# HotplateReflowSchematic.net
KiCad netlist of a schematic drawn in EAGLE
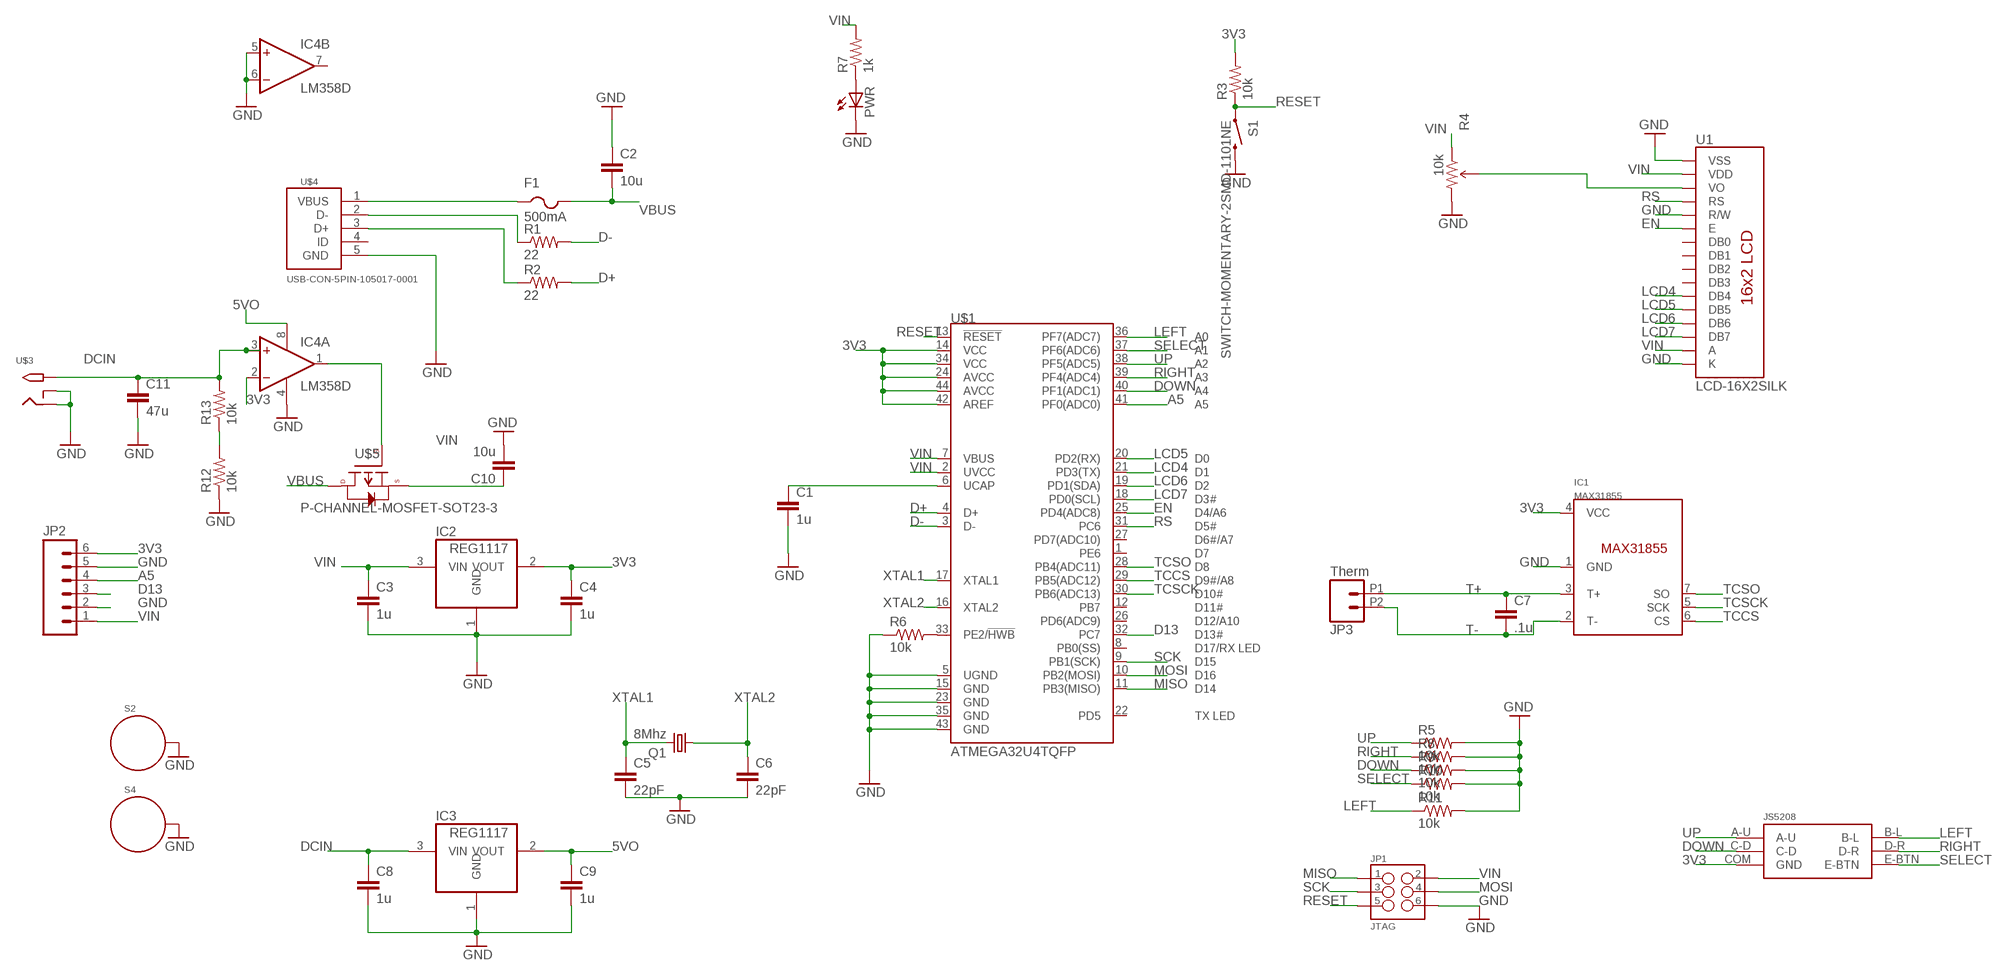
[diagram p0: schematic, sheet 1]

(export (version "E")
  (design (tool "Eeschema 10.0.6"))
  (components
    (comp (ref "C1")
      (value "1u")
      (footprint "eagle-import:0603-CAP")
      (libsource (lib "eagle-import") (part "SparkFun-Passives_CAP0603-CAP"))
    )
    (comp (ref "C2")
      (value "10u")
      (footprint "eagle-import:0603-CAP")
      (libsource (lib "eagle-import") (part "SparkFun-Passives_CAP0603-CAP"))
    )
    (comp (ref "C3")
      (value "1u")
      (footprint "eagle-import:0603-CAP")
      (libsource (lib "eagle-import") (part "SparkFun-Passives_CAP0603-CAP"))
    )
    (comp (ref "C4")
      (value "1u")
      (footprint "eagle-import:0603-CAP")
      (libsource (lib "eagle-import") (part "SparkFun-Passives_CAP0603-CAP"))
    )
    (comp (ref "C5")
      (value "22pF")
      (footprint "eagle-import:0603-CAP")
      (libsource (lib "eagle-import") (part "SparkFun-Passives_CAP0603-CAP"))
    )
    (comp (ref "C6")
      (value "22pF")
      (footprint "eagle-import:0603-CAP")
      (libsource (lib "eagle-import") (part "SparkFun-Passives_CAP0603-CAP"))
    )
    (comp (ref "C7")
      (value ".1u")
      (footprint "eagle-import:0603-CAP")
      (libsource (lib "eagle-import") (part "SparkFun-Passives_CAP0603-CAP"))
    )
    (comp (ref "C8")
      (value "1u")
      (footprint "eagle-import:0603-CAP")
      (libsource (lib "eagle-import") (part "CAP0603-CAP"))
    )
    (comp (ref "C9")
      (value "1u")
      (footprint "eagle-import:0603-CAP")
      (libsource (lib "eagle-import") (part "CAP0603-CAP"))
    )
    (comp (ref "C10")
      (value "10u")
      (footprint "eagle-import:0603-CAP")
      (libsource (lib "eagle-import") (part "CAP0603-CAP"))
    )
    (comp (ref "C11")
      (value "47u")
      (footprint "eagle-import:0603-CAP")
      (libsource (lib "eagle-import") (part "SparkFun-Passives_CAP0603-CAP"))
    )
    (comp (ref "F1")
      (value "500mA")
      (footprint "eagle-import:1812")
      (libsource (lib "eagle-import") (part "PTCFUSE-1812"))
    )
    (comp (ref "IC1")
      (value "MAX31855")
      (footprint "eagle-import:SOIC8")
      (libsource (lib "eagle-import") (part "MAX31855"))
    )
    (comp (ref "IC2")
      (value "REG1117")
      (footprint "eagle-import:SOT223")
      (libsource (lib "eagle-import") (part "REG1117"))
    )
    (comp (ref "IC3")
      (value "REG1117")
      (footprint "eagle-import:SOT223")
      (libsource (lib "eagle-import") (part "REG1117"))
    )
    (comp (ref "IC4")
      (value "LM358D")
      (footprint "eagle-import:SO08")
      (libsource (lib "eagle-import") (part "LM358D"))
    )
    (comp (ref "JP1")
      (value "JTAG")
      (footprint "eagle-import:2X3-SHROUDED")
      (libsource (lib "eagle-import") (part "M03X2SHROUD"))
    )
    (comp (ref "JP2")
      (value "M06LOCK")
      (footprint "eagle-import:1X06_LOCK")
      (libsource (lib "eagle-import") (part "M06LOCK"))
    )
    (comp (ref "JP3")
      (value "Therm")
      (footprint "eagle-import:1X02_2.54_SCREWTERM")
      (libsource (lib "eagle-import") (part "M022.54MM_SCREWTERM"))
    )
    (comp (ref "PWR")
      (value "LEDCHIP-LED0603")
      (footprint "eagle-import:CHIP-LED0603")
      (libsource (lib "eagle-import") (part "LEDCHIP-LED0603"))
    )
    (comp (ref "Q1")
      (value "8Mhz")
      (footprint "eagle-import:HC49UP")
      (libsource (lib "eagle-import") (part "CRYSTALHC49UP"))
    )
    (comp (ref "R1")
      (value "22")
      (footprint "eagle-import:0603-RES")
      (libsource (lib "eagle-import") (part "RESISTOR0603-RES"))
    )
    (comp (ref "R2")
      (value "22")
      (footprint "eagle-import:0603-RES")
      (libsource (lib "eagle-import") (part "RESISTOR0603-RES"))
    )
    (comp (ref "R3")
      (value "10k")
      (footprint "eagle-import:0603-RES")
      (libsource (lib "eagle-import") (part "RESISTOR0603-RES"))
    )
    (comp (ref "R4")
      (value "10k")
      (footprint "eagle-import:TRIMPOT-5MM-V2")
      (libsource (lib "eagle-import") (part "TRIMPOT"))
    )
    (comp (ref "R5")
      (value "10k")
      (footprint "eagle-import:0603-RES")
      (libsource (lib "eagle-import") (part "RESISTOR0603-RES"))
    )
    (comp (ref "R6")
      (value "10k")
      (footprint "eagle-import:0603-RES")
      (libsource (lib "eagle-import") (part "RESISTOR0603"))
    )
    (comp (ref "R7")
      (value "1k")
      (footprint "eagle-import:0603-RES")
      (libsource (lib "eagle-import") (part "RESISTOR0603"))
    )
    (comp (ref "R8")
      (value "10k")
      (footprint "eagle-import:0603-RES")
      (libsource (lib "eagle-import") (part "RESISTOR0603-RES"))
    )
    (comp (ref "R9")
      (value "10k")
      (footprint "eagle-import:0603-RES")
      (libsource (lib "eagle-import") (part "RESISTOR0603-RES"))
    )
    (comp (ref "R10")
      (value "10k")
      (footprint "eagle-import:0603-RES")
      (libsource (lib "eagle-import") (part "RESISTOR0603-RES"))
    )
    (comp (ref "R11")
      (value "10k")
      (footprint "eagle-import:0603-RES")
      (libsource (lib "eagle-import") (part "RESISTOR0603-RES"))
    )
    (comp (ref "R12")
      (value "10k")
      (footprint "eagle-import:0603-RES")
      (libsource (lib "eagle-import") (part "RESISTOR0603-RES"))
    )
    (comp (ref "R13")
      (value "10k")
      (footprint "eagle-import:0603-RES")
      (libsource (lib "eagle-import") (part "RESISTOR0603-RES"))
    )
    (comp (ref "S1")
      (value "SWITCH-MOMENTARY-2SMD-1101NE")
      (footprint "eagle-import:TACTILE-SWITCH-1101NE")
      (libsource (lib "eagle-import") (part "SWITCH-MOMENTARY-2SMD-1101NE"))
    )
    (comp (ref "S2")
      (value "STANDOFF_ELECTRICAL")
      (footprint "eagle-import:STANDOFF-ELECTRICAL")
      (libsource (lib "eagle-import") (part "STANDOFF_ELECTRICAL"))
    )
    (comp (ref "S4")
      (value "STANDOFF_ELECTRICAL")
      (footprint "eagle-import:STANDOFF-ELECTRICAL")
      (libsource (lib "eagle-import") (part "STANDOFF_ELECTRICAL"))
    )
    (comp (ref "U$1")
      (value "ATMEGA32U4TQFP")
      (footprint "eagle-import:SPARKFUN-DIGITALIC_TQFP44")
      (libsource (lib "eagle-import") (part "ATMEGA32U4TQFP"))
    )
    (comp (ref "U$2")
      (value "JS5208")
      (footprint "eagle-import:JS5208_PKG")
      (libsource (lib "eagle-import") (part "JS5208"))
    )
    (comp (ref "U$3")
      (value "2.1MMJACKTHM")
      (footprint "eagle-import:PJ-102A")
      (libsource (lib "eagle-import") (part "2.1MMJACKTHM"))
    )
    (comp (ref "U$4")
      (value "USB-CON-5PIN-105017-0001")
      (footprint "eagle-import:USB-MICRO-MOLEX-105017-0001")
      (libsource (lib "eagle-import") (part "USB-CON-5PIN-105017-0001"))
    )
    (comp (ref "U$5")
      (value "P-CHANNEL-MOSFET-SOT23-3")
      (footprint "eagle-import:SOT23-3")
      (libsource (lib "eagle-import") (part "P-CHANNEL-MOSFET-SOT23-3"))
    )
    (comp (ref "U1")
      (value "LCD-16X2SILK")
      (footprint "eagle-import:LCD-16X2")
      (libsource (lib "eagle-import") (part "LCD-16X2SILK"))
    )
  )
  (nets
    (net (code "1") (name "/3V3") (class "Default")
      (node (ref "C4") (pin "1") (pinfunction "1_1") (pintype "passive"))
      (node (ref "IC1") (pin "4") (pinfunction "VCC_4") (pintype "power_in"))
      (node (ref "IC2") (pin "2") (pinfunction "VOUT_2") (pintype "output"))
      (node (ref "IC4") (pin "2") (pinfunction "-IN_2") (pintype "input"))
      (node (ref "JP2") (pin "6") (pinfunction "6_6") (pintype "passive"))
      (node (ref "R3") (pin "2") (pinfunction "2_2") (pintype "passive"))
      (node (ref "U$1") (pin "14") (pinfunction "VCC_14") (pintype "bidirectional"))
      (node (ref "U$1") (pin "24") (pinfunction "AVCC_24") (pintype "bidirectional"))
      (node (ref "U$1") (pin "34") (pinfunction "VCC_34") (pintype "bidirectional"))
      (node (ref "U$1") (pin "42") (pinfunction "AREF_42") (pintype "bidirectional"))
      (node (ref "U$1") (pin "44") (pinfunction "AVCC_44") (pintype "bidirectional"))
      (node (ref "U$2") (pin "COM") (pinfunction "GND_COM") (pintype "bidirectional"))
    )
    (net (code "2") (name "/5VO") (class "Default")
      (node (ref "C9") (pin "1") (pinfunction "1_1") (pintype "passive"))
      (node (ref "IC3") (pin "2") (pinfunction "VOUT_2") (pintype "output"))
      (node (ref "IC4") (pin "8") (pinfunction "V+_8") (pintype "power_in"))
    )
    (net (code "3") (name "/A5") (class "Default")
      (node (ref "JP2") (pin "4") (pinfunction "4_4") (pintype "passive"))
      (node (ref "U$1") (pin "41") (pinfunction "PF0(ADC0)_41") (pintype "bidirectional"))
    )
    (net (code "4") (name "/D+") (class "Default")
      (node (ref "R2") (pin "2") (pinfunction "2_2") (pintype "passive"))
      (node (ref "U$1") (pin "4") (pinfunction "D+_4") (pintype "bidirectional"))
    )
    (net (code "5") (name "/D-") (class "Default")
      (node (ref "R1") (pin "2") (pinfunction "2_2") (pintype "passive"))
      (node (ref "U$1") (pin "3") (pinfunction "D-_3") (pintype "bidirectional"))
    )
    (net (code "6") (name "/D13") (class "Default")
      (node (ref "JP2") (pin "3") (pinfunction "3_3") (pintype "passive"))
      (node (ref "U$1") (pin "32") (pinfunction "PC7_32") (pintype "bidirectional"))
    )
    (net (code "7") (name "/DCIN") (class "Default")
      (node (ref "C11") (pin "1") (pinfunction "1_1") (pintype "passive"))
      (node (ref "C8") (pin "1") (pinfunction "1_1") (pintype "passive"))
      (node (ref "IC3") (pin "3") (pinfunction "VIN_3") (pintype "input"))
      (node (ref "IC4") (pin "3") (pinfunction "+IN_3") (pintype "input"))
      (node (ref "R13") (pin "2") (pinfunction "2_2") (pintype "passive"))
      (node (ref "U$3") (pin "TIP") (pinfunction "TIP_TIP") (pintype "bidirectional"))
    )
    (net (code "8") (name "/DOWN") (class "Default")
      (node (ref "R9") (pin "1") (pinfunction "1_1") (pintype "passive"))
      (node (ref "U$1") (pin "40") (pinfunction "PF1(ADC1)_40") (pintype "bidirectional"))
      (node (ref "U$2") (pin "C-D") (pinfunction "C-D_C-D") (pintype "bidirectional"))
    )
    (net (code "9") (name "/EN") (class "Default")
      (node (ref "U$1") (pin "25") (pinfunction "PD4(ADC8)_25") (pintype "bidirectional"))
      (node (ref "U1") (pin "6") (pinfunction "E_6") (pintype "input"))
    )
    (net (code "10") (name "/LCD4") (class "Default")
      (node (ref "U$1") (pin "21") (pinfunction "PD3(TX)_21") (pintype "bidirectional"))
      (node (ref "U1") (pin "11") (pinfunction "DB4_11") (pintype "bidirectional"))
    )
    (net (code "11") (name "/LCD5") (class "Default")
      (node (ref "U$1") (pin "20") (pinfunction "PD2(RX)_20") (pintype "bidirectional"))
      (node (ref "U1") (pin "12") (pinfunction "DB5_12") (pintype "bidirectional"))
    )
    (net (code "12") (name "/LCD6") (class "Default")
      (node (ref "U$1") (pin "19") (pinfunction "PD1(SDA)_19") (pintype "bidirectional"))
      (node (ref "U1") (pin "13") (pinfunction "DB6_13") (pintype "bidirectional"))
    )
    (net (code "13") (name "/LCD7") (class "Default")
      (node (ref "U$1") (pin "18") (pinfunction "PD0(SCL)_18") (pintype "bidirectional"))
      (node (ref "U1") (pin "14") (pinfunction "DB7_14") (pintype "bidirectional"))
    )
    (net (code "14") (name "/LEFT") (class "Default")
      (node (ref "R11") (pin "1") (pinfunction "1_1") (pintype "passive"))
      (node (ref "U$1") (pin "36") (pinfunction "PF7(ADC7)_36") (pintype "bidirectional"))
      (node (ref "U$2") (pin "B-L") (pinfunction "B-L_B-L") (pintype "bidirectional"))
    )
    (net (code "15") (name "/MISO") (class "Default")
      (node (ref "JP1") (pin "1") (pinfunction "1_1") (pintype "bidirectional"))
      (node (ref "U$1") (pin "11") (pinfunction "PB3(MISO)_11") (pintype "bidirectional"))
    )
    (net (code "16") (name "/MOSI") (class "Default")
      (node (ref "JP1") (pin "4") (pinfunction "4_4") (pintype "bidirectional"))
      (node (ref "U$1") (pin "10") (pinfunction "PB2(MOSI)_10") (pintype "bidirectional"))
    )
    (net (code "17") (name "/RESET") (class "Default")
      (node (ref "JP1") (pin "5") (pinfunction "5_5") (pintype "bidirectional"))
      (node (ref "R3") (pin "1") (pinfunction "1_1") (pintype "passive"))
      (node (ref "S1") (pin "1") (pinfunction "1_1") (pintype "passive"))
      (node (ref "U$1") (pin "13") (pinfunction "~{RESET}_13") (pintype "bidirectional"))
    )
    (net (code "18") (name "/RIGHT") (class "Default")
      (node (ref "R8") (pin "1") (pinfunction "1_1") (pintype "passive"))
      (node (ref "U$1") (pin "39") (pinfunction "PF4(ADC4)_39") (pintype "bidirectional"))
      (node (ref "U$2") (pin "D-R") (pinfunction "D-R_D-R") (pintype "bidirectional"))
    )
    (net (code "19") (name "/RS") (class "Default")
      (node (ref "U$1") (pin "31") (pinfunction "PC6_31") (pintype "bidirectional"))
      (node (ref "U1") (pin "4") (pinfunction "RS_4") (pintype "input"))
    )
    (net (code "20") (name "/SCK") (class "Default")
      (node (ref "JP1") (pin "3") (pinfunction "3_3") (pintype "bidirectional"))
      (node (ref "U$1") (pin "9") (pinfunction "PB1(SCK)_9") (pintype "bidirectional"))
    )
    (net (code "21") (name "/SELECT") (class "Default")
      (node (ref "R10") (pin "1") (pinfunction "1_1") (pintype "passive"))
      (node (ref "U$1") (pin "37") (pinfunction "PF6(ADC6)_37") (pintype "bidirectional"))
      (node (ref "U$2") (pin "E-BTN") (pinfunction "E-BTN_E-BTN") (pintype "bidirectional"))
    )
    (net (code "22") (name "/T+") (class "Default")
      (node (ref "C7") (pin "1") (pinfunction "1_1") (pintype "passive"))
      (node (ref "IC1") (pin "3") (pinfunction "T+_3") (pintype "input"))
      (node (ref "JP3") (pin "P1") (pinfunction "1_P1") (pintype "passive"))
    )
    (net (code "23") (name "/T-") (class "Default")
      (node (ref "C7") (pin "2") (pinfunction "2_2") (pintype "passive"))
      (node (ref "IC1") (pin "2") (pinfunction "T-_2") (pintype "input"))
      (node (ref "JP3") (pin "P2") (pinfunction "2_P2") (pintype "passive"))
    )
    (net (code "24") (name "/TCCS") (class "Default")
      (node (ref "IC1") (pin "6") (pinfunction "CS_6") (pintype "input"))
      (node (ref "U$1") (pin "29") (pinfunction "PB5(ADC12)_29") (pintype "bidirectional"))
    )
    (net (code "25") (name "/TCSCK") (class "Default")
      (node (ref "IC1") (pin "5") (pinfunction "SCK_5") (pintype "input"))
      (node (ref "U$1") (pin "30") (pinfunction "PB6(ADC13)_30") (pintype "bidirectional"))
    )
    (net (code "26") (name "/TCSO") (class "Default")
      (node (ref "IC1") (pin "7") (pinfunction "SO_7") (pintype "output"))
      (node (ref "U$1") (pin "28") (pinfunction "PB4(ADC11)_28") (pintype "bidirectional"))
    )
    (net (code "27") (name "/UP") (class "Default")
      (node (ref "R5") (pin "1") (pinfunction "1_1") (pintype "passive"))
      (node (ref "U$1") (pin "38") (pinfunction "PF5(ADC5)_38") (pintype "bidirectional"))
      (node (ref "U$2") (pin "A-U") (pinfunction "A-U_A-U") (pintype "bidirectional"))
    )
    (net (code "28") (name "/VBUS") (class "Default")
      (node (ref "C2") (pin "2") (pinfunction "2_2") (pintype "passive"))
      (node (ref "F1") (pin "2") (pinfunction "2_2") (pintype "passive"))
      (node (ref "U$5") (pin "3") (pinfunction "D_3") (pintype "passive"))
    )
    (net (code "29") (name "/VIN") (class "Default")
      (node (ref "C10") (pin "1") (pinfunction "1_1") (pintype "passive"))
      (node (ref "C3") (pin "1") (pinfunction "1_1") (pintype "passive"))
      (node (ref "IC2") (pin "3") (pinfunction "VIN_3") (pintype "input"))
      (node (ref "JP1") (pin "2") (pinfunction "2_2") (pintype "bidirectional"))
      (node (ref "JP2") (pin "1") (pinfunction "1_1") (pintype "passive"))
      (node (ref "R4") (pin "A") (pinfunction "CCW_A") (pintype "passive"))
      (node (ref "R7") (pin "2") (pinfunction "2_2") (pintype "passive"))
      (node (ref "U$1") (pin "2") (pinfunction "UVCC_2") (pintype "bidirectional"))
      (node (ref "U$1") (pin "7") (pinfunction "VBUS_7") (pintype "bidirectional"))
      (node (ref "U$5") (pin "2") (pinfunction "S_2") (pintype "passive"))
      (node (ref "U1") (pin "15") (pinfunction "A_15") (pintype "power_in"))
      (node (ref "U1") (pin "2") (pinfunction "VDD_2") (pintype "power_in"))
    )
    (net (code "30") (name "/XTAL1") (class "Default")
      (node (ref "C5") (pin "1") (pinfunction "1_1") (pintype "passive"))
      (node (ref "Q1") (pin "2") (pinfunction "2_2") (pintype "passive"))
      (node (ref "U$1") (pin "17") (pinfunction "XTAL1_17") (pintype "bidirectional"))
    )
    (net (code "31") (name "/XTAL2") (class "Default")
      (node (ref "C6") (pin "1") (pinfunction "1_1") (pintype "passive"))
      (node (ref "Q1") (pin "1") (pinfunction "1_1") (pintype "passive"))
      (node (ref "U$1") (pin "16") (pinfunction "XTAL2_16") (pintype "bidirectional"))
    )
    (net (code "32") (name "GND") (class "Default")
      (node (ref "C1") (pin "2") (pinfunction "2_2") (pintype "passive"))
      (node (ref "C10") (pin "2") (pinfunction "2_2") (pintype "passive"))
      (node (ref "C11") (pin "2") (pinfunction "2_2") (pintype "passive"))
      (node (ref "C2") (pin "1") (pinfunction "1_1") (pintype "passive"))
      (node (ref "C3") (pin "2") (pinfunction "2_2") (pintype "passive"))
      (node (ref "C4") (pin "2") (pinfunction "2_2") (pintype "passive"))
      (node (ref "C5") (pin "2") (pinfunction "2_2") (pintype "passive"))
      (node (ref "C6") (pin "2") (pinfunction "2_2") (pintype "passive"))
      (node (ref "C8") (pin "2") (pinfunction "2_2") (pintype "passive"))
      (node (ref "C9") (pin "2") (pinfunction "2_2") (pintype "passive"))
      (node (ref "IC1") (pin "1") (pinfunction "GND_1") (pintype "power_in"))
      (node (ref "IC2") (pin "1") (pinfunction "GND_1") (pintype "power_in"))
      (node (ref "IC3") (pin "1") (pinfunction "GND_1") (pintype "power_in"))
      (node (ref "IC4") (pin "4") (pinfunction "V-_4") (pintype "power_in"))
      (node (ref "IC4") (pin "5") (pinfunction "+IN_5") (pintype "input"))
      (node (ref "IC4") (pin "6") (pinfunction "-IN_6") (pintype "input"))
      (node (ref "JP1") (pin "6") (pinfunction "6_6") (pintype "bidirectional"))
      (node (ref "JP2") (pin "2") (pinfunction "2_2") (pintype "passive"))
      (node (ref "JP2") (pin "5") (pinfunction "5_5") (pintype "passive"))
      (node (ref "PWR") (pin "C") (pinfunction "C_C") (pintype "passive"))
      (node (ref "R10") (pin "2") (pinfunction "2_2") (pintype "passive"))
      (node (ref "R11") (pin "2") (pinfunction "2_2") (pintype "passive"))
      (node (ref "R12") (pin "1") (pinfunction "1_1") (pintype "passive"))
      (node (ref "R4") (pin "C") (pinfunction "CW_C") (pintype "passive"))
      (node (ref "R5") (pin "2") (pinfunction "2_2") (pintype "passive"))
      (node (ref "R6") (pin "1") (pinfunction "1_1") (pintype "passive"))
      (node (ref "R8") (pin "2") (pinfunction "2_2") (pintype "passive"))
      (node (ref "R9") (pin "2") (pinfunction "2_2") (pintype "passive"))
      (node (ref "S1") (pin "2") (pinfunction "2_2") (pintype "passive"))
      (node (ref "S2") (pin "P1") (pinfunction "P$1_P1") (pintype "bidirectional"))
      (node (ref "S4") (pin "P1") (pinfunction "P$1_P1") (pintype "bidirectional"))
      (node (ref "U$1") (pin "15") (pinfunction "GND_15") (pintype "bidirectional"))
      (node (ref "U$1") (pin "23") (pinfunction "GND_23") (pintype "bidirectional"))
      (node (ref "U$1") (pin "35") (pinfunction "GND_35") (pintype "bidirectional"))
      (node (ref "U$1") (pin "43") (pinfunction "GND_43") (pintype "bidirectional"))
      (node (ref "U$1") (pin "5") (pinfunction "UGND_5") (pintype "bidirectional"))
      (node (ref "U$3") (pin "RING") (pinfunction "RING_RING") (pintype "bidirectional"))
      (node (ref "U$3") (pin "RING_SW") (pinfunction "RING_SW_RING_SW") (pintype "bidirectional"))
      (node (ref "U$4") (pin "5") (pinfunction "GND_5") (pintype "power_in"))
      (node (ref "U1") (pin "1") (pinfunction "VSS_1") (pintype "power_in"))
      (node (ref "U1") (pin "16") (pinfunction "K_16") (pintype "power_in"))
      (node (ref "U1") (pin "5") (pinfunction "R/W_5") (pintype "input"))
    )
    (net (code "33") (name "Net-(IC4A-OUT)") (class "Default")
      (node (ref "IC4") (pin "1") (pinfunction "OUT_1") (pintype "output"))
      (node (ref "U$5") (pin "1") (pinfunction "G_1") (pintype "passive"))
    )
    (net (code "34") (name "Net-(PWR-PadA)") (class "Default")
      (node (ref "PWR") (pin "A") (pinfunction "A_A") (pintype "passive"))
      (node (ref "R7") (pin "1") (pinfunction "1_1") (pintype "passive"))
    )
    (net (code "35") (name "Net-(R4-WIPER)") (class "Default")
      (node (ref "R4") (pin "B") (pinfunction "WIPER_B") (pintype "passive"))
      (node (ref "U1") (pin "3") (pinfunction "VO_3") (pintype "bidirectional"))
    )
    (net (code "36") (name "Net-(R12-Pad2)") (class "Default")
      (node (ref "R12") (pin "2") (pinfunction "2_2") (pintype "passive"))
      (node (ref "R13") (pin "1") (pinfunction "1_1") (pintype "passive"))
    )
    (net (code "37") (name "Net-(U$1-PE2{slash}~{HWB})") (class "Default")
      (node (ref "R6") (pin "2") (pinfunction "2_2") (pintype "passive"))
      (node (ref "U$1") (pin "33") (pinfunction "PE2/~{HWB}_33") (pintype "bidirectional"))
    )
    (net (code "38") (name "Net-(U$1-UCAP)") (class "Default")
      (node (ref "C1") (pin "1") (pinfunction "1_1") (pintype "passive"))
      (node (ref "U$1") (pin "6") (pinfunction "UCAP_6") (pintype "bidirectional"))
    )
    (net (code "39") (name "Net-(U$4-D+)") (class "Default")
      (node (ref "R2") (pin "1") (pinfunction "1_1") (pintype "passive"))
      (node (ref "U$4") (pin "3") (pinfunction "D+_3") (pintype "bidirectional"))
    )
    (net (code "40") (name "Net-(U$4-D-)") (class "Default")
      (node (ref "R1") (pin "1") (pinfunction "1_1") (pintype "passive"))
      (node (ref "U$4") (pin "2") (pinfunction "D-_2") (pintype "bidirectional"))
    )
    (net (code "41") (name "Net-(U$4-VBUS)") (class "Default")
      (node (ref "F1") (pin "1") (pinfunction "1_1") (pintype "passive"))
      (node (ref "U$4") (pin "1") (pinfunction "VBUS_1") (pintype "power_in"))
    )
    (net (code "42") (name "unconnected-(IC4B-OUT-Pad7)") (class "Default")
      (node (ref "IC4") (pin "7") (pinfunction "OUT_7") (pintype "output"))
    )
    (net (code "43") (name "unconnected-(U$1-PB0(SS)-Pad8)") (class "Default")
      (node (ref "U$1") (pin "8") (pinfunction "PB0(SS)_8") (pintype "bidirectional"))
    )
    (net (code "44") (name "unconnected-(U$1-PB7-Pad12)") (class "Default")
      (node (ref "U$1") (pin "12") (pinfunction "PB7_12") (pintype "bidirectional"))
    )
    (net (code "45") (name "unconnected-(U$1-PD5-Pad22)") (class "Default")
      (node (ref "U$1") (pin "22") (pinfunction "PD5_22") (pintype "bidirectional"))
    )
    (net (code "46") (name "unconnected-(U$1-PD6(ADC9)-Pad26)") (class "Default")
      (node (ref "U$1") (pin "26") (pinfunction "PD6(ADC9)_26") (pintype "bidirectional"))
    )
    (net (code "47") (name "unconnected-(U$1-PD7(ADC10)-Pad27)") (class "Default")
      (node (ref "U$1") (pin "27") (pinfunction "PD7(ADC10)_27") (pintype "bidirectional"))
    )
    (net (code "48") (name "unconnected-(U$1-PE6-Pad1)") (class "Default")
      (node (ref "U$1") (pin "1") (pinfunction "PE6_1") (pintype "bidirectional"))
    )
    (net (code "49") (name "unconnected-(U$4-ID-Pad4)") (class "Default")
      (node (ref "U$4") (pin "4") (pinfunction "ID_4") (pintype "bidirectional"))
    )
    (net (code "50") (name "unconnected-(U1-DB0-Pad7)") (class "Default")
      (node (ref "U1") (pin "7") (pinfunction "DB0_7") (pintype "bidirectional"))
    )
    (net (code "51") (name "unconnected-(U1-DB1-Pad8)") (class "Default")
      (node (ref "U1") (pin "8") (pinfunction "DB1_8") (pintype "bidirectional"))
    )
    (net (code "52") (name "unconnected-(U1-DB2-Pad9)") (class "Default")
      (node (ref "U1") (pin "9") (pinfunction "DB2_9") (pintype "bidirectional"))
    )
    (net (code "53") (name "unconnected-(U1-DB3-Pad10)") (class "Default")
      (node (ref "U1") (pin "10") (pinfunction "DB3_10") (pintype "bidirectional"))
    )
  )
)
